# opamp.net
KiCad netlist of a schematic drawn in Altium Designer
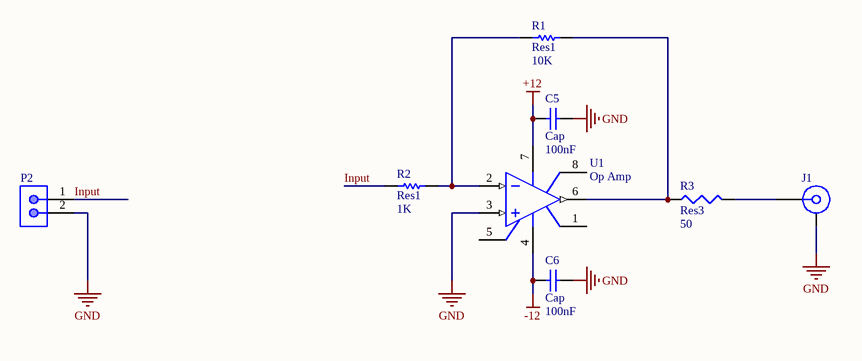
[diagram p0: opamp.SchDoc]

(export (version "E")
  (design (tool "Eeschema 10.0.6"))
  (components
    (comp (ref "C5")
      (value "Cap")
      (footprint "RAD-0.3")
      (description "Capacitor")
      (fields (field (name "ALTIUM_VALUE") "100nF") (field (name "PUBLISHER") "Altium Limited"))
      (libsource (lib "Miscellaneous Devices") (part "Cap"))
    )
    (comp (ref "C6")
      (value "Cap")
      (footprint "RAD-0.3")
      (description "Capacitor")
      (fields (field (name "ALTIUM_VALUE") "100nF") (field (name "PUBLISHER") "Altium Limited"))
      (libsource (lib "Miscellaneous Devices") (part "Cap"))
    )
    (comp (ref "J1")
      (value "51K204-400A5")
      (footprint "ROS-51K204-400A5_V")
      (description "BNC 50R Right Angle Jack, Panel Feedthrough, Up to 10 GHz, -55 to 155 degC")
      (fields (field (name "MANUFACTURER") "Rosenberger"))
      (libsource (lib "Altium Content Vault") (part "ROS-CN-1F-RF1"))
    )
    (comp (ref "P2")
      (value "22-27-2021")
      (footprint "MOLX-22-27-2021_V")
      (fields (field (name "MANUFACTURER") "Molex") (field (name "PARTNUMBER") "0022272021"))
      (libsource (lib "Altium Content Vault") (part "CN-1P-M-R2"))
    )
    (comp (ref "R1")
      (value "Res1")
      (footprint "AXIAL-0.3")
      (description "Resistor")
      (fields (field (name "ALTIUM_VALUE") "10K") (field (name "PUBLISHER") "Altium Limited"))
      (libsource (lib "Miscellaneous Devices") (part "Res1"))
    )
    (comp (ref "R2")
      (value "Res1")
      (footprint "AXIAL-0.3")
      (description "Resistor")
      (fields (field (name "ALTIUM_VALUE") "1K") (field (name "PUBLISHER") "Altium Limited"))
      (libsource (lib "Miscellaneous Devices") (part "Res1"))
    )
    (comp (ref "R3")
      (value "Res3")
      (footprint "J1-0603")
      (description "Resistor")
      (fields (field (name "ALTIUM_VALUE") "50") (field (name "PUBLISHER") "Altium Limited"))
      (libsource (lib "Miscellaneous Devices") (part "Res3"))
    )
    (comp (ref "U1")
      (value "Op Amp")
      (footprint "DIP-8")
      (description "FET Operational Amplifier")
      (fields (field (name "PUBLISHER") "Altium Limited"))
      (libsource (lib "Miscellaneous Devices") (part "Op Amp"))
    )
  )
  (nets
    (net (code "1") (name "+12") (class "Default")
      (node (ref "C5") (pin "2") (pinfunction "2_2") (pintype "passive"))
      (node (ref "U1") (pin "7") (pinfunction "V+_7") (pintype "power_in"))
    )
    (net (code "2") (name "-12") (class "Default")
      (node (ref "C6") (pin "2") (pinfunction "2_2") (pintype "passive"))
      (node (ref "U1") (pin "4") (pinfunction "V-_4") (pintype "power_in"))
    )
    (net (code "3") (name "/Input") (class "Default")
      (node (ref "P2") (pin "1") (pinfunction "1_1") (pintype "passive"))
      (node (ref "R2") (pin "1") (pinfunction "1_1") (pintype "passive"))
    )
    (net (code "4") (name "GND") (class "Default")
      (node (ref "C5") (pin "1") (pinfunction "1_1") (pintype "passive"))
      (node (ref "C6") (pin "1") (pinfunction "1_1") (pintype "passive"))
      (node (ref "J1") (pin "MH") (pinfunction "MH_MH") (pintype "passive"))
      (node (ref "P2") (pin "2") (pinfunction "2_2") (pintype "passive"))
      (node (ref "U1") (pin "3") (pinfunction "IN+_3") (pintype "input"))
    )
    (net (code "5") (name "Net-(J1-Pad1)") (class "Default")
      (node (ref "J1") (pin "1") (pinfunction "1_1") (pintype "passive"))
      (node (ref "R3") (pin "2") (pinfunction "2_2") (pintype "passive"))
    )
    (net (code "6") (name "Net-(U1-IN-)") (class "Default")
      (node (ref "R1") (pin "1") (pinfunction "1_1") (pintype "passive"))
      (node (ref "R2") (pin "2") (pinfunction "2_2") (pintype "passive"))
      (node (ref "U1") (pin "2") (pinfunction "IN-_2") (pintype "input"))
    )
    (net (code "7") (name "Net-(U1-OUT)") (class "Default")
      (node (ref "R1") (pin "2") (pinfunction "2_2") (pintype "passive"))
      (node (ref "R3") (pin "1") (pinfunction "1_1") (pintype "passive"))
      (node (ref "U1") (pin "6") (pinfunction "OUT_6") (pintype "output"))
    )
    (net (code "8") (name "unconnected-(U1-OS_NUL-Pad1)") (class "Default")
      (node (ref "U1") (pin "1") (pinfunction "OS_NUL_1") (pintype "passive"))
    )
    (net (code "9") (name "unconnected-(U1-OS_NUL-Pad5)") (class "Default")
      (node (ref "U1") (pin "5") (pinfunction "OS_NUL_5") (pintype "passive"))
    )
    (net (code "10") (name "unconnected-(U1-TAB-Pad8)") (class "Default")
      (node (ref "U1") (pin "8") (pinfunction "TAB_8") (pintype "passive"))
    )
  )
)
